# 3525.net
KiCad netlist of a schematic drawn in EAGLE
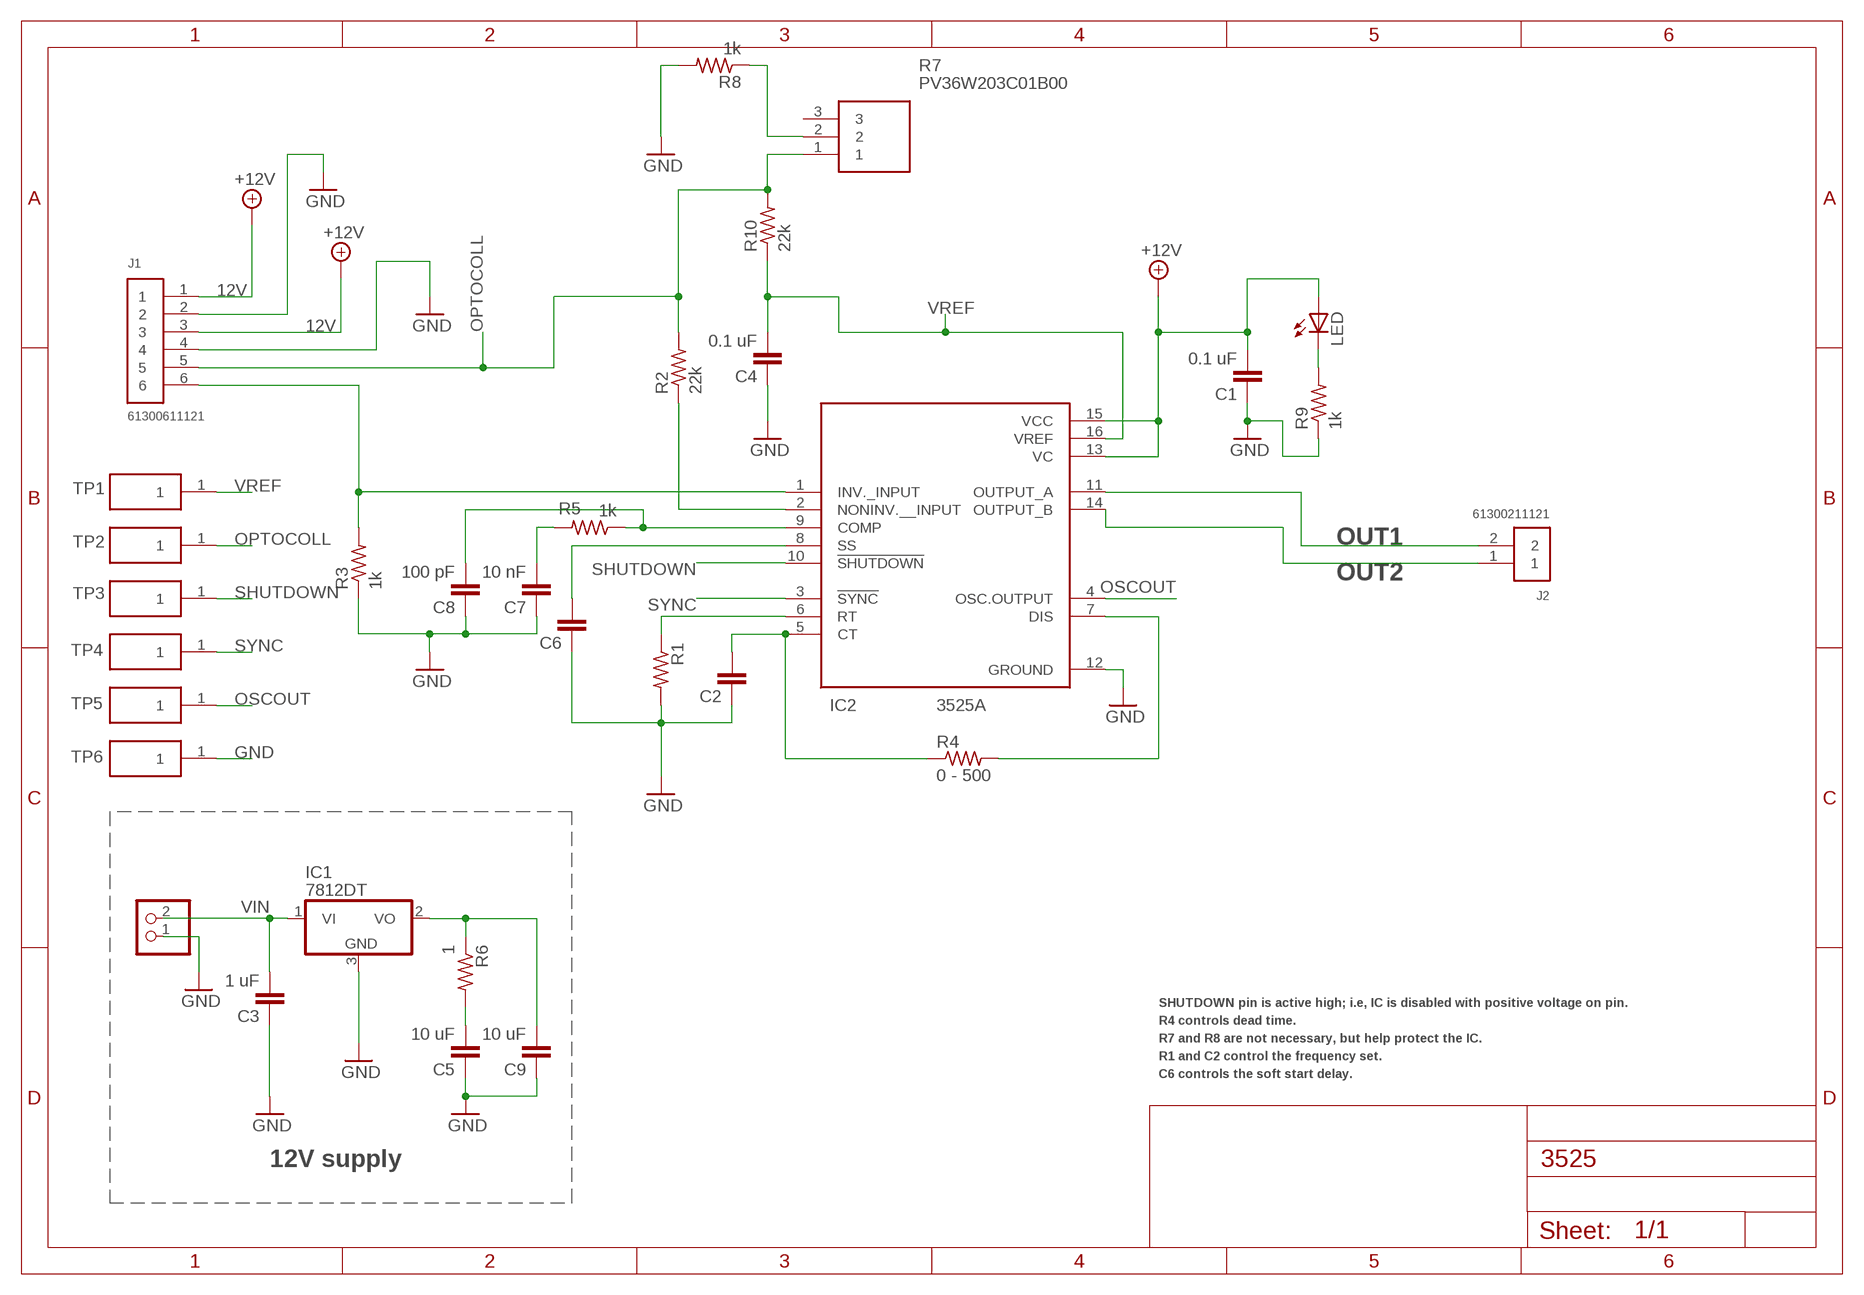
[diagram p0: schematic, sheet 1]

(export (version "E")
  (design (tool "Eeschema 10.0.6"))
  (components
    (comp (ref "C1")
      (value "0.1 uF")
      (footprint "eagle-import:C0805")
      (libsource (lib "eagle-import") (part "rcl_334_C-EUC0805"))
    )
    (comp (ref "C2")
      (value "C-EUC0805K")
      (footprint "eagle-import:C0805K")
      (libsource (lib "eagle-import") (part "C-EUC0805K"))
    )
    (comp (ref "C3")
      (value "1 uF")
      (footprint "eagle-import:C0805K")
      (libsource (lib "eagle-import") (part "C-EUC0805K"))
    )
    (comp (ref "C4")
      (value "0.1 uF")
      (footprint "eagle-import:C0805K")
      (libsource (lib "eagle-import") (part "C-EUC0805K"))
    )
    (comp (ref "C5")
      (value "10 uF")
      (footprint "eagle-import:C0805K")
      (libsource (lib "eagle-import") (part "C-EUC0805K"))
    )
    (comp (ref "C6")
      (value "C-EUC0805K")
      (footprint "eagle-import:C0805K")
      (libsource (lib "eagle-import") (part "C-EUC0805K"))
    )
    (comp (ref "C7")
      (value "10 nF")
      (footprint "eagle-import:C0805K")
      (libsource (lib "eagle-import") (part "C-EUC0805K"))
    )
    (comp (ref "C8")
      (value "100 pF")
      (footprint "eagle-import:C0805K")
      (libsource (lib "eagle-import") (part "C-EUC0805K"))
    )
    (comp (ref "C9")
      (value "10 uF")
      (footprint "eagle-import:C0805K")
      (libsource (lib "eagle-import") (part "C-EUC0805K"))
    )
    (comp (ref "IC1")
      (value "7812DT")
      (footprint "eagle-import:TO252")
      (libsource (lib "eagle-import") (part "78DT12"))
    )
    (comp (ref "IC2")
      (value "3525A")
      (footprint "eagle-import:SOIC127P1030X265-16N")
      (fields
        (field (name "MANUFACTURER_PART_NUMBER") "SG3525ADWR2G")
        (field (name "MOUSER_PART_NUMBER") "863-SG3525ADWR2G")
      )
      (libsource (lib "eagle-import") (part "SG3525ADWR2G"))
    )
    (comp (ref "J1")
      (value "61300611121")
      (footprint "eagle-import:61300611121")
      (fields
        (field (name "DIGI_KEY_PART_NUMBER") "732-5319-ND")
        (field (name "MANUFACTURER") "Wurth Electronics Inc.")
        (field (name "CREATED_BY") "PCBLayout.com")
      )
      (libsource (lib "eagle-import") (part "61300611121"))
    )
    (comp (ref "J2")
      (value "61300211121")
      (footprint "eagle-import:61300211121")
      (fields
        (field (name "DIGI_KEY_PART_NUMBER") "732-5315-ND")
        (field (name "MANUFACTURER") "Wurth Electronics Inc.")
        (field (name "CREATED_BY") "PCBLayout.com")
      )
      (libsource (lib "eagle-import") (part "61300211121"))
    )
    (comp (ref "LED")
      (value "LEDCHIPLED_0805")
      (footprint "eagle-import:CHIPLED_0805")
      (libsource (lib "eagle-import") (part "LEDCHIPLED_0805"))
    )
    (comp (ref "R1")
      (value "R-US_R0805")
      (footprint "eagle-import:R0805")
      (libsource (lib "eagle-import") (part "R-US_R0805"))
    )
    (comp (ref "R2")
      (value "22k")
      (footprint "eagle-import:R0805")
      (libsource (lib "eagle-import") (part "R-US_R0805"))
    )
    (comp (ref "R3")
      (value "1k")
      (footprint "eagle-import:R0805")
      (libsource (lib "eagle-import") (part "R-US_R0805"))
    )
    (comp (ref "R4")
      (value "0 - 500")
      (footprint "eagle-import:R0805")
      (libsource (lib "eagle-import") (part "R-US_R0805"))
    )
    (comp (ref "R5")
      (value "1k")
      (footprint "eagle-import:R0805")
      (libsource (lib "eagle-import") (part "R-US_R0805"))
    )
    (comp (ref "R6")
      (value "1")
      (footprint "eagle-import:R0805")
      (libsource (lib "eagle-import") (part "R-US_R0805"))
    )
    (comp (ref "R7")
      (value "PV36W203C01B00")
      (footprint "eagle-import:PV36W201C01B00")
      (fields (field (name "MOUSER_PART_NUMBER") "81-PV36W203C01B00"))
      (libsource (lib "eagle-import") (part "PV36W203C01B00"))
    )
    (comp (ref "R8")
      (value "1k")
      (footprint "eagle-import:R0805")
      (libsource (lib "eagle-import") (part "R-US_R0805"))
    )
    (comp (ref "R9")
      (value "1k")
      (footprint "eagle-import:R0805")
      (libsource (lib "eagle-import") (part "R-US_R0805"))
    )
    (comp (ref "R10")
      (value "22k")
      (footprint "eagle-import:R0805")
      (libsource (lib "eagle-import") (part "R-US_R0805"))
    )
    (comp (ref "SUPPLY")
      (value "PINHD-1X2")
      (footprint "eagle-import:1X02")
      (libsource (lib "eagle-import") (part "PINHD-1X2"))
    )
    (comp (ref "TP1")
      (value "RCT-0C")
      (footprint "eagle-import:RCT-0C")
      (fields (field (name "MOUSER_PART_NUMBER") "279-RCT-0C"))
      (libsource (lib "eagle-import") (part "RCT-0C"))
    )
    (comp (ref "TP2")
      (value "RCT-0C")
      (footprint "eagle-import:RCT-0C")
      (fields (field (name "MOUSER_PART_NUMBER") "279-RCT-0C"))
      (libsource (lib "eagle-import") (part "RCT-0C"))
    )
    (comp (ref "TP3")
      (value "RCT-0C")
      (footprint "eagle-import:RCT-0C")
      (fields (field (name "MOUSER_PART_NUMBER") "279-RCT-0C"))
      (libsource (lib "eagle-import") (part "RCT-0C"))
    )
    (comp (ref "TP4")
      (value "RCT-0C")
      (footprint "eagle-import:RCT-0C")
      (fields (field (name "MOUSER_PART_NUMBER") "279-RCT-0C"))
      (libsource (lib "eagle-import") (part "RCT-0C"))
    )
    (comp (ref "TP5")
      (value "RCT-0C")
      (footprint "eagle-import:RCT-0C")
      (fields (field (name "MOUSER_PART_NUMBER") "279-RCT-0C"))
      (libsource (lib "eagle-import") (part "RCT-0C"))
    )
    (comp (ref "TP6")
      (value "RCT-0C")
      (footprint "eagle-import:RCT-0C")
      (fields (field (name "MOUSER_PART_NUMBER") "279-RCT-0C"))
      (libsource (lib "eagle-import") (part "RCT-0C"))
    )
  )
  (nets
    (net (code "1") (name "+12V") (class "Default")
      (node (ref "C1") (pin "2") (pinfunction "2_2") (pintype "passive"))
      (node (ref "C9") (pin "2") (pinfunction "2_2") (pintype "passive"))
      (node (ref "IC1") (pin "2") (pinfunction "VO_2") (pintype "passive"))
      (node (ref "IC2") (pin "13") (pinfunction "VC_13") (pintype "bidirectional"))
      (node (ref "IC2") (pin "15") (pinfunction "VCC_15") (pintype "bidirectional"))
      (node (ref "J1") (pin "1") (pinfunction "1_1") (pintype "passive"))
      (node (ref "J1") (pin "3") (pinfunction "3_3") (pintype "passive"))
      (node (ref "LED") (pin "A") (pinfunction "A_A") (pintype "passive"))
      (node (ref "R6") (pin "1") (pinfunction "1_1") (pintype "passive"))
    )
    (net (code "2") (name "/OPTOCOLL") (class "Default")
      (node (ref "J1") (pin "5") (pinfunction "5_5") (pintype "passive"))
      (node (ref "R10") (pin "2") (pinfunction "2_2") (pintype "passive"))
      (node (ref "R2") (pin "2") (pinfunction "2_2") (pintype "passive"))
      (node (ref "R7") (pin "1") (pinfunction "1_1") (pintype "bidirectional"))
      (node (ref "TP2") (pin "1") (pinfunction "1_1") (pintype "bidirectional"))
    )
    (net (code "3") (name "/OSCOUT") (class "Default")
      (node (ref "IC2") (pin "4") (pinfunction "OSC.OUTPUT_4") (pintype "bidirectional"))
      (node (ref "TP5") (pin "1") (pinfunction "1_1") (pintype "bidirectional"))
    )
    (net (code "4") (name "/OUT1") (class "Default")
      (node (ref "IC2") (pin "11") (pinfunction "OUTPUT_A_11") (pintype "bidirectional"))
      (node (ref "J2") (pin "2") (pinfunction "2_2") (pintype "passive"))
    )
    (net (code "5") (name "/OUT2") (class "Default")
      (node (ref "IC2") (pin "14") (pinfunction "OUTPUT_B_14") (pintype "bidirectional"))
      (node (ref "J2") (pin "1") (pinfunction "1_1") (pintype "passive"))
    )
    (net (code "6") (name "/SHUTDOWN") (class "Default")
      (node (ref "IC2") (pin "10") (pinfunction "~{SHUTDOWN}_10") (pintype "bidirectional"))
      (node (ref "TP3") (pin "1") (pinfunction "1_1") (pintype "bidirectional"))
    )
    (net (code "7") (name "/SYNC") (class "Default")
      (node (ref "IC2") (pin "3") (pinfunction "~{SYNC}_3") (pintype "bidirectional"))
      (node (ref "TP4") (pin "1") (pinfunction "1_1") (pintype "bidirectional"))
    )
    (net (code "8") (name "/VIN") (class "Default")
      (node (ref "C3") (pin "2") (pinfunction "2_2") (pintype "passive"))
      (node (ref "IC1") (pin "1") (pinfunction "VI_1") (pintype "input"))
      (node (ref "SUPPLY") (pin "2") (pinfunction "2_2") (pintype "passive"))
    )
    (net (code "9") (name "/VREF") (class "Default")
      (node (ref "C4") (pin "2") (pinfunction "2_2") (pintype "passive"))
      (node (ref "IC2") (pin "16") (pinfunction "VREF_16") (pintype "bidirectional"))
      (node (ref "R10") (pin "1") (pinfunction "1_1") (pintype "passive"))
      (node (ref "TP1") (pin "1") (pinfunction "1_1") (pintype "bidirectional"))
    )
    (net (code "10") (name "GND") (class "Default")
      (node (ref "C1") (pin "1") (pinfunction "1_1") (pintype "passive"))
      (node (ref "C2") (pin "1") (pinfunction "1_1") (pintype "passive"))
      (node (ref "C3") (pin "1") (pinfunction "1_1") (pintype "passive"))
      (node (ref "C4") (pin "1") (pinfunction "1_1") (pintype "passive"))
      (node (ref "C5") (pin "1") (pinfunction "1_1") (pintype "passive"))
      (node (ref "C6") (pin "1") (pinfunction "1_1") (pintype "passive"))
      (node (ref "C7") (pin "1") (pinfunction "1_1") (pintype "passive"))
      (node (ref "C8") (pin "1") (pinfunction "1_1") (pintype "passive"))
      (node (ref "C9") (pin "1") (pinfunction "1_1") (pintype "passive"))
      (node (ref "IC1") (pin "3") (pinfunction "GND_3") (pintype "passive"))
      (node (ref "IC2") (pin "12") (pinfunction "GROUND_12") (pintype "bidirectional"))
      (node (ref "J1") (pin "2") (pinfunction "2_2") (pintype "passive"))
      (node (ref "J1") (pin "4") (pinfunction "4_4") (pintype "passive"))
      (node (ref "R1") (pin "2") (pinfunction "2_2") (pintype "passive"))
      (node (ref "R3") (pin "1") (pinfunction "1_1") (pintype "passive"))
      (node (ref "R8") (pin "2") (pinfunction "2_2") (pintype "passive"))
      (node (ref "R9") (pin "1") (pinfunction "1_1") (pintype "passive"))
      (node (ref "SUPPLY") (pin "1") (pinfunction "1_1") (pintype "passive"))
      (node (ref "TP6") (pin "1") (pinfunction "1_1") (pintype "bidirectional"))
    )
    (net (code "11") (name "Net-(C5-Pad2)") (class "Default")
      (node (ref "C5") (pin "2") (pinfunction "2_2") (pintype "passive"))
      (node (ref "R6") (pin "2") (pinfunction "2_2") (pintype "passive"))
    )
    (net (code "12") (name "Net-(C7-Pad2)") (class "Default")
      (node (ref "C7") (pin "2") (pinfunction "2_2") (pintype "passive"))
      (node (ref "R5") (pin "2") (pinfunction "2_2") (pintype "passive"))
    )
    (net (code "13") (name "Net-(IC2-COMP)") (class "Default")
      (node (ref "C8") (pin "2") (pinfunction "2_2") (pintype "passive"))
      (node (ref "IC2") (pin "9") (pinfunction "COMP_9") (pintype "bidirectional"))
      (node (ref "R5") (pin "1") (pinfunction "1_1") (pintype "passive"))
    )
    (net (code "14") (name "Net-(IC2-CT)") (class "Default")
      (node (ref "C2") (pin "2") (pinfunction "2_2") (pintype "passive"))
      (node (ref "IC2") (pin "5") (pinfunction "CT_5") (pintype "bidirectional"))
      (node (ref "R4") (pin "1") (pinfunction "1_1") (pintype "passive"))
    )
    (net (code "15") (name "Net-(IC2-DIS)") (class "Default")
      (node (ref "IC2") (pin "7") (pinfunction "DIS_7") (pintype "bidirectional"))
      (node (ref "R4") (pin "2") (pinfunction "2_2") (pintype "passive"))
    )
    (net (code "16") (name "Net-(IC2-INV._INPUT)") (class "Default")
      (node (ref "IC2") (pin "1") (pinfunction "INV._INPUT_1") (pintype "bidirectional"))
      (node (ref "J1") (pin "6") (pinfunction "6_6") (pintype "passive"))
      (node (ref "R3") (pin "2") (pinfunction "2_2") (pintype "passive"))
    )
    (net (code "17") (name "Net-(IC2-NONINV.__INPUT)") (class "Default")
      (node (ref "IC2") (pin "2") (pinfunction "NONINV.__INPUT_2") (pintype "bidirectional"))
      (node (ref "R2") (pin "1") (pinfunction "1_1") (pintype "passive"))
    )
    (net (code "18") (name "Net-(IC2-RT)") (class "Default")
      (node (ref "IC2") (pin "6") (pinfunction "RT_6") (pintype "bidirectional"))
      (node (ref "R1") (pin "1") (pinfunction "1_1") (pintype "passive"))
    )
    (net (code "19") (name "Net-(IC2-SS)") (class "Default")
      (node (ref "C6") (pin "2") (pinfunction "2_2") (pintype "passive"))
      (node (ref "IC2") (pin "8") (pinfunction "SS_8") (pintype "bidirectional"))
    )
    (net (code "20") (name "Net-(LED-PadC)") (class "Default")
      (node (ref "LED") (pin "C") (pinfunction "C_C") (pintype "passive"))
      (node (ref "R9") (pin "2") (pinfunction "2_2") (pintype "passive"))
    )
    (net (code "21") (name "Net-(R7-Pad2)") (class "Default")
      (node (ref "R7") (pin "2") (pinfunction "2_2") (pintype "bidirectional"))
      (node (ref "R8") (pin "1") (pinfunction "1_1") (pintype "passive"))
    )
    (net (code "22") (name "unconnected-(R7-Pad3)") (class "Default")
      (node (ref "R7") (pin "3") (pinfunction "3_3") (pintype "bidirectional"))
    )
  )
)
